# nymph.net
KiCad netlist of a schematic drawn in EAGLE
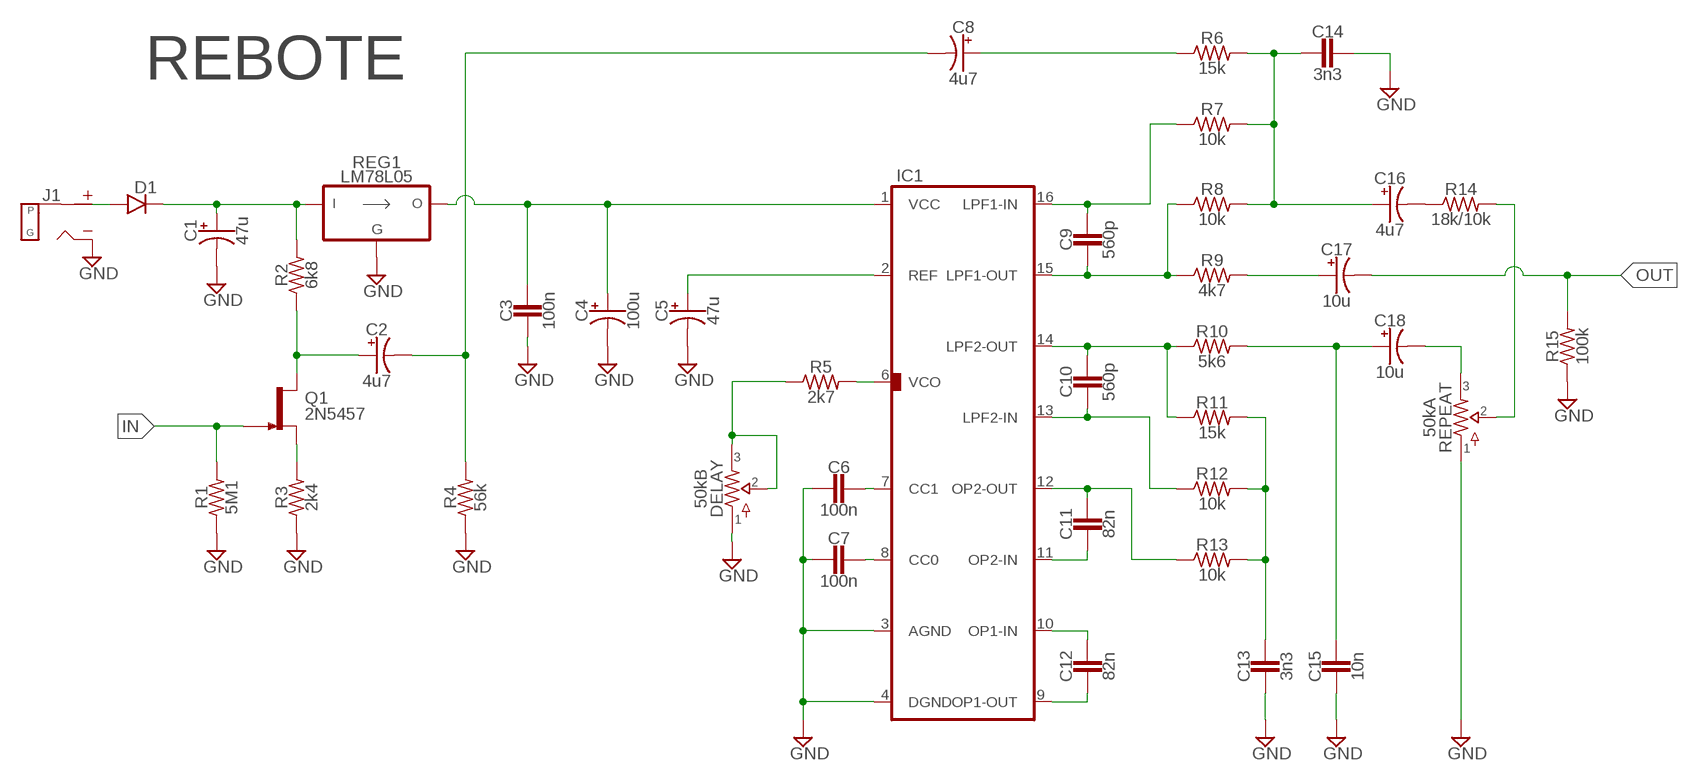
[diagram p0: schematic, sheet 1]

(export (version "E")
  (design (tool "Eeschema 10.0.6"))
  (components
    (comp (ref "C1")
      (value "47u")
      (footprint "eagle-import:050_020_1")
      (libsource (lib "eagle-import") (part "0501"))
    )
    (comp (ref "C2")
      (value "4u7")
      (footprint "eagle-import:050_020_1")
      (libsource (lib "eagle-import") (part "0501"))
    )
    (comp (ref "C3")
      (value "100n")
      (footprint "eagle-import:050X030_025_2")
      (libsource (lib "eagle-import") (part "CER/FILM2"))
    )
    (comp (ref "C4")
      (value "100u")
      (footprint "eagle-import:050_020_1")
      (libsource (lib "eagle-import") (part "0501"))
    )
    (comp (ref "C5")
      (value "47u")
      (footprint "eagle-import:050_020_1")
      (libsource (lib "eagle-import") (part "0501"))
    )
    (comp (ref "C6")
      (value "100n")
      (footprint "eagle-import:050X030_025_2")
      (libsource (lib "eagle-import") (part "CER/FILM2"))
    )
    (comp (ref "C7")
      (value "100n")
      (footprint "eagle-import:050X030_025_2")
      (libsource (lib "eagle-import") (part "CER/FILM2"))
    )
    (comp (ref "C8")
      (value "4u7")
      (footprint "eagle-import:050_020_1")
      (libsource (lib "eagle-import") (part "0501"))
    )
    (comp (ref "C9")
      (value "560p")
      (footprint "eagle-import:050X030_025_2")
      (libsource (lib "eagle-import") (part "CER/FILM2"))
    )
    (comp (ref "C10")
      (value "560p")
      (footprint "eagle-import:050X030_025_2")
      (libsource (lib "eagle-import") (part "CER/FILM2"))
    )
    (comp (ref "C11")
      (value "82n")
      (footprint "eagle-import:050X030_025_2")
      (libsource (lib "eagle-import") (part "CER/FILM2"))
    )
    (comp (ref "C12")
      (value "82n")
      (footprint "eagle-import:050X030_025_2")
      (libsource (lib "eagle-import") (part "CER/FILM2"))
    )
    (comp (ref "C13")
      (value "3n3")
      (footprint "eagle-import:050X030_025_2")
      (libsource (lib "eagle-import") (part "CER/FILM2"))
    )
    (comp (ref "C14")
      (value "3n3")
      (footprint "eagle-import:050X030_025_2")
      (libsource (lib "eagle-import") (part "CER/FILM2"))
    )
    (comp (ref "C15")
      (value "10n")
      (footprint "eagle-import:050X030_025_2")
      (libsource (lib "eagle-import") (part "CER/FILM2"))
    )
    (comp (ref "C16")
      (value "4u7")
      (footprint "eagle-import:050_020_1")
      (libsource (lib "eagle-import") (part "0501"))
    )
    (comp (ref "C17")
      (value "10u")
      (footprint "eagle-import:050_020_1")
      (libsource (lib "eagle-import") (part "0501"))
    )
    (comp (ref "C18")
      (value "10u")
      (footprint "eagle-import:050_020_1")
      (libsource (lib "eagle-import") (part "0501"))
    )
    (comp (ref "D1")
      (value "DO41.3")
      (footprint "eagle-import:DO41-3")
      (libsource (lib "eagle-import") (part "DO41.3"))
    )
    (comp (ref "DELAY")
      (value "50kB")
      (footprint "eagle-import:PADS_SMALL")
      (libsource (lib "eagle-import") (part "POTSSMALL_PADS"))
    )
    (comp (ref "IC1")
      (value "PT2399TH")
      (footprint "eagle-import:DIL16")
      (libsource (lib "eagle-import") (part "PT2399TH"))
    )
    (comp (ref "J1")
      (value "DC_MONO")
      (footprint "eagle-import:DC")
      (libsource (lib "eagle-import") (part "DC_MONO"))
    )
    (comp (ref "Q1")
      (value "2N5457")
      (footprint "eagle-import:TO92-")
      (libsource (lib "eagle-import") (part "2N5457"))
    )
    (comp (ref "R1")
      (value "5M1")
      (footprint "eagle-import:R0207_2V")
      (libsource (lib "eagle-import") (part "R_.2"))
    )
    (comp (ref "R2")
      (value "6k8")
      (footprint "eagle-import:R0207_2V")
      (libsource (lib "eagle-import") (part "R_.2"))
    )
    (comp (ref "R3")
      (value "2k4")
      (footprint "eagle-import:R0207_2V")
      (libsource (lib "eagle-import") (part "R_.2"))
    )
    (comp (ref "R4")
      (value "56k")
      (footprint "eagle-import:R0207_2V")
      (libsource (lib "eagle-import") (part "R_.2"))
    )
    (comp (ref "R5")
      (value "2k7")
      (footprint "eagle-import:R0207_2V")
      (libsource (lib "eagle-import") (part "R_.2"))
    )
    (comp (ref "R6")
      (value "15k")
      (footprint "eagle-import:R0207_2V")
      (libsource (lib "eagle-import") (part "R_.2"))
    )
    (comp (ref "R7")
      (value "10k")
      (footprint "eagle-import:R0207_2V")
      (libsource (lib "eagle-import") (part "R_.2"))
    )
    (comp (ref "R8")
      (value "10k")
      (footprint "eagle-import:R0207_2V")
      (libsource (lib "eagle-import") (part "R_.2"))
    )
    (comp (ref "R9")
      (value "4k7")
      (footprint "eagle-import:R0207_2V")
      (libsource (lib "eagle-import") (part "R_.2"))
    )
    (comp (ref "R10")
      (value "5k6")
      (footprint "eagle-import:R0207_2V")
      (libsource (lib "eagle-import") (part "R_.2"))
    )
    (comp (ref "R11")
      (value "15k")
      (footprint "eagle-import:R0207_2V")
      (libsource (lib "eagle-import") (part "R_.2"))
    )
    (comp (ref "R12")
      (value "10k")
      (footprint "eagle-import:R0207_2V")
      (libsource (lib "eagle-import") (part "R_.2"))
    )
    (comp (ref "R13")
      (value "10k")
      (footprint "eagle-import:R0207_2V")
      (libsource (lib "eagle-import") (part "R_.2"))
    )
    (comp (ref "R14")
      (value "18k/10k")
      (footprint "eagle-import:R0207_2V")
      (libsource (lib "eagle-import") (part "R_.2"))
    )
    (comp (ref "R15")
      (value "100k")
      (footprint "eagle-import:R0207_2V")
      (libsource (lib "eagle-import") (part "R_.2"))
    )
    (comp (ref "REG1")
      (value "LM78L05")
      (footprint "eagle-import:TO92-")
      (libsource (lib "eagle-import") (part "LM78L05"))
    )
    (comp (ref "REPEAT")
      (value "50kA")
      (footprint "eagle-import:PADS_SMALL")
      (libsource (lib "eagle-import") (part "POTSSMALL_PADS"))
    )
  )
  (nets
    (net (code "1") (name "GND") (class "Default")
      (node (ref "C1") (pin "-") (pinfunction "-_-") (pintype "passive"))
      (node (ref "C13") (pin "2") (pinfunction "2_2") (pintype "passive"))
      (node (ref "C14") (pin "1") (pinfunction "1_1") (pintype "passive"))
      (node (ref "C15") (pin "2") (pinfunction "2_2") (pintype "passive"))
      (node (ref "C3") (pin "2") (pinfunction "2_2") (pintype "passive"))
      (node (ref "C4") (pin "-") (pinfunction "-_-") (pintype "passive"))
      (node (ref "C5") (pin "-") (pinfunction "-_-") (pintype "passive"))
      (node (ref "C6") (pin "2") (pinfunction "2_2") (pintype "passive"))
      (node (ref "C7") (pin "2") (pinfunction "2_2") (pintype "passive"))
      (node (ref "DELAY") (pin "1") (pinfunction "1_1") (pintype "passive"))
      (node (ref "IC1") (pin "3") (pinfunction "AGND_3") (pintype "power_in"))
      (node (ref "IC1") (pin "4") (pinfunction "DGND_4") (pintype "power_in"))
      (node (ref "J1") (pin "S") (pinfunction "SLEEVE_S") (pintype "passive"))
      (node (ref "R1") (pin "1") (pinfunction "1_1") (pintype "passive"))
      (node (ref "R15") (pin "1") (pinfunction "1_1") (pintype "passive"))
      (node (ref "R3") (pin "1") (pinfunction "1_1") (pintype "passive"))
      (node (ref "R4") (pin "1") (pinfunction "1_1") (pintype "passive"))
      (node (ref "REG1") (pin "2") (pinfunction "GND_2") (pintype "passive"))
      (node (ref "REPEAT") (pin "1") (pinfunction "1_1") (pintype "passive"))
    )
    (net (code "2") (name "IN") (class "Default")
      (node (ref "Q1") (pin "1") (pinfunction "G_1") (pintype "passive"))
      (node (ref "R1") (pin "2") (pinfunction "2_2") (pintype "passive"))
    )
    (net (code "3") (name "Net-(C2-Pad-)") (class "Default")
      (node (ref "C2") (pin "-") (pinfunction "-_-") (pintype "passive"))
      (node (ref "C8") (pin "-") (pinfunction "-_-") (pintype "passive"))
      (node (ref "R4") (pin "2") (pinfunction "2_2") (pintype "passive"))
    )
    (net (code "4") (name "Net-(C8-Pad+)") (class "Default")
      (node (ref "C8") (pin "+") (pinfunction "+_+") (pintype "passive"))
      (node (ref "R6") (pin "1") (pinfunction "1_1") (pintype "passive"))
    )
    (net (code "5") (name "Net-(C13-Pad1)") (class "Default")
      (node (ref "C13") (pin "1") (pinfunction "1_1") (pintype "passive"))
      (node (ref "R11") (pin "2") (pinfunction "2_2") (pintype "passive"))
      (node (ref "R12") (pin "2") (pinfunction "2_2") (pintype "passive"))
      (node (ref "R13") (pin "2") (pinfunction "2_2") (pintype "passive"))
    )
    (net (code "6") (name "Net-(C14-Pad2)") (class "Default")
      (node (ref "C14") (pin "2") (pinfunction "2_2") (pintype "passive"))
      (node (ref "C16") (pin "+") (pinfunction "+_+") (pintype "passive"))
      (node (ref "R6") (pin "2") (pinfunction "2_2") (pintype "passive"))
      (node (ref "R7") (pin "2") (pinfunction "2_2") (pintype "passive"))
      (node (ref "R8") (pin "2") (pinfunction "2_2") (pintype "passive"))
    )
    (net (code "7") (name "Net-(C15-Pad1)") (class "Default")
      (node (ref "C15") (pin "1") (pinfunction "1_1") (pintype "passive"))
      (node (ref "C18") (pin "+") (pinfunction "+_+") (pintype "passive"))
      (node (ref "R10") (pin "2") (pinfunction "2_2") (pintype "passive"))
    )
    (net (code "8") (name "Net-(C16-Pad-)") (class "Default")
      (node (ref "C16") (pin "-") (pinfunction "-_-") (pintype "passive"))
      (node (ref "R14") (pin "1") (pinfunction "1_1") (pintype "passive"))
    )
    (net (code "9") (name "Net-(C17-Pad+)") (class "Default")
      (node (ref "C17") (pin "+") (pinfunction "+_+") (pintype "passive"))
      (node (ref "R9") (pin "2") (pinfunction "2_2") (pintype "passive"))
    )
    (net (code "10") (name "Net-(C18-Pad-)") (class "Default")
      (node (ref "C18") (pin "-") (pinfunction "-_-") (pintype "passive"))
      (node (ref "REPEAT") (pin "3") (pinfunction "3_3") (pintype "passive"))
    )
    (net (code "11") (name "Net-(DELAY-Pad2)") (class "Default")
      (node (ref "DELAY") (pin "2") (pinfunction "2_2") (pintype "passive"))
      (node (ref "DELAY") (pin "3") (pinfunction "3_3") (pintype "passive"))
      (node (ref "R5") (pin "1") (pinfunction "1_1") (pintype "passive"))
    )
    (net (code "12") (name "Net-(IC1-CC0)") (class "Default")
      (node (ref "C7") (pin "1") (pinfunction "1_1") (pintype "passive"))
      (node (ref "IC1") (pin "8") (pinfunction "CC0_8") (pintype "input"))
    )
    (net (code "13") (name "Net-(IC1-CC1)") (class "Default")
      (node (ref "C6") (pin "1") (pinfunction "1_1") (pintype "passive"))
      (node (ref "IC1") (pin "7") (pinfunction "CC1_7") (pintype "input"))
    )
    (net (code "14") (name "Net-(IC1-LPF1-IN)") (class "Default")
      (node (ref "C9") (pin "1") (pinfunction "1_1") (pintype "passive"))
      (node (ref "IC1") (pin "16") (pinfunction "LPF1-IN_16") (pintype "input"))
      (node (ref "R7") (pin "1") (pinfunction "1_1") (pintype "passive"))
    )
    (net (code "15") (name "Net-(IC1-LPF1-OUT)") (class "Default")
      (node (ref "C9") (pin "2") (pinfunction "2_2") (pintype "passive"))
      (node (ref "IC1") (pin "15") (pinfunction "LPF1-OUT_15") (pintype "output"))
      (node (ref "R8") (pin "1") (pinfunction "1_1") (pintype "passive"))
      (node (ref "R9") (pin "1") (pinfunction "1_1") (pintype "passive"))
    )
    (net (code "16") (name "Net-(IC1-LPF2-IN)") (class "Default")
      (node (ref "C10") (pin "2") (pinfunction "2_2") (pintype "passive"))
      (node (ref "IC1") (pin "13") (pinfunction "LPF2-IN_13") (pintype "input"))
      (node (ref "R12") (pin "1") (pinfunction "1_1") (pintype "passive"))
    )
    (net (code "17") (name "Net-(IC1-LPF2-OUT)") (class "Default")
      (node (ref "C10") (pin "1") (pinfunction "1_1") (pintype "passive"))
      (node (ref "IC1") (pin "14") (pinfunction "LPF2-OUT_14") (pintype "output"))
      (node (ref "R10") (pin "1") (pinfunction "1_1") (pintype "passive"))
      (node (ref "R11") (pin "1") (pinfunction "1_1") (pintype "passive"))
    )
    (net (code "18") (name "Net-(IC1-OP1-IN)") (class "Default")
      (node (ref "C12") (pin "1") (pinfunction "1_1") (pintype "passive"))
      (node (ref "IC1") (pin "10") (pinfunction "OP1-IN_10") (pintype "input"))
    )
    (net (code "19") (name "Net-(IC1-OP1-OUT)") (class "Default")
      (node (ref "C12") (pin "2") (pinfunction "2_2") (pintype "passive"))
      (node (ref "IC1") (pin "9") (pinfunction "OP1-OUT_9") (pintype "output"))
    )
    (net (code "20") (name "Net-(IC1-OP2-IN)") (class "Default")
      (node (ref "C11") (pin "2") (pinfunction "2_2") (pintype "passive"))
      (node (ref "IC1") (pin "11") (pinfunction "OP2-IN_11") (pintype "input"))
    )
    (net (code "21") (name "Net-(IC1-OP2-OUT)") (class "Default")
      (node (ref "C11") (pin "1") (pinfunction "1_1") (pintype "passive"))
      (node (ref "IC1") (pin "12") (pinfunction "OP2-OUT_12") (pintype "output"))
      (node (ref "R13") (pin "1") (pinfunction "1_1") (pintype "passive"))
    )
    (net (code "22") (name "Net-(IC1-REF)") (class "Default")
      (node (ref "C5") (pin "+") (pinfunction "+_+") (pintype "passive"))
      (node (ref "IC1") (pin "2") (pinfunction "REF_2") (pintype "input"))
    )
    (net (code "23") (name "Net-(IC1-VCC)") (class "Default")
      (node (ref "C3") (pin "1") (pinfunction "1_1") (pintype "passive"))
      (node (ref "C4") (pin "+") (pinfunction "+_+") (pintype "passive"))
      (node (ref "IC1") (pin "1") (pinfunction "VCC_1") (pintype "power_in"))
      (node (ref "REG1") (pin "3") (pinfunction "VO_3") (pintype "passive"))
    )
    (net (code "24") (name "Net-(IC1-VCO)") (class "Default")
      (node (ref "IC1") (pin "6") (pinfunction "VCO_6") (pintype "input"))
      (node (ref "R5") (pin "2") (pinfunction "2_2") (pintype "passive"))
    )
    (net (code "25") (name "Net-(J1-TIP)") (class "Default")
      (node (ref "D1") (pin "A") (pinfunction "A_A") (pintype "passive"))
      (node (ref "J1") (pin "T") (pinfunction "TIP_T") (pintype "passive"))
    )
    (net (code "26") (name "Net-(Q1-D)") (class "Default")
      (node (ref "C2") (pin "+") (pinfunction "+_+") (pintype "passive"))
      (node (ref "Q1") (pin "3") (pinfunction "D_3") (pintype "passive"))
      (node (ref "R2") (pin "1") (pinfunction "1_1") (pintype "passive"))
    )
    (net (code "27") (name "Net-(Q1-S)") (class "Default")
      (node (ref "Q1") (pin "2") (pinfunction "S_2") (pintype "passive"))
      (node (ref "R3") (pin "2") (pinfunction "2_2") (pintype "passive"))
    )
    (net (code "28") (name "Net-(R14-Pad2)") (class "Default")
      (node (ref "R14") (pin "2") (pinfunction "2_2") (pintype "passive"))
      (node (ref "REPEAT") (pin "2") (pinfunction "2_2") (pintype "passive"))
    )
    (net (code "29") (name "Net-(REG1-VI)") (class "Default")
      (node (ref "C1") (pin "+") (pinfunction "+_+") (pintype "passive"))
      (node (ref "D1") (pin "C") (pinfunction "C_C") (pintype "passive"))
      (node (ref "R2") (pin "2") (pinfunction "2_2") (pintype "passive"))
      (node (ref "REG1") (pin "1") (pinfunction "VI_1") (pintype "input"))
    )
    (net (code "30") (name "OUT") (class "Default")
      (node (ref "C17") (pin "-") (pinfunction "-_-") (pintype "passive"))
      (node (ref "R15") (pin "2") (pinfunction "2_2") (pintype "passive"))
    )
  )
)
